# Buck_Boost_Converter_B.net
KiCad netlist of a schematic drawn in Altium Designer
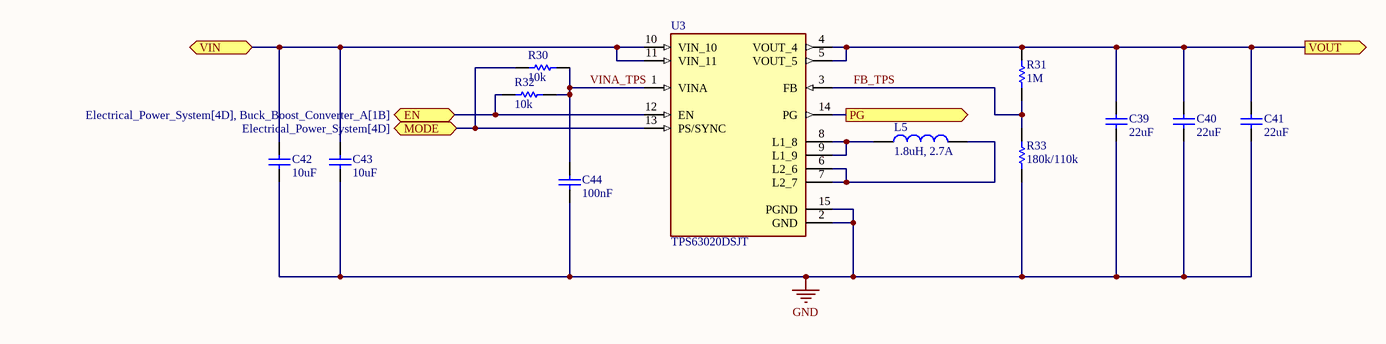
[diagram p0: Buck_Boost_Converter_B.SchDoc]

(export (version "E")
  (design (tool "Eeschema 10.0.6"))
  (components
    (comp (ref "C39")
      (value "22uF")
      (footprint "CAP-SM-0603")
      (description "Capacitor")
      (fields (field (name "Comment") "Cap Non-Pol SMD"))
      (libsource (lib "PIF_Library") (part "Cap Non-Pol SMD"))
    )
    (comp (ref "C40")
      (value "22uF")
      (footprint "CAP-SM-0603")
      (description "Capacitor")
      (fields (field (name "Comment") "Cap Non-Pol SMD"))
      (libsource (lib "PIF_Library") (part "Cap Non-Pol SMD"))
    )
    (comp (ref "C41")
      (value "22uF")
      (footprint "CAP-SM-0603")
      (description "Capacitor")
      (fields (field (name "Comment") "Cap Non-Pol SMD"))
      (libsource (lib "PIF_Library") (part "Cap Non-Pol SMD"))
    )
    (comp (ref "C42")
      (value "10uF")
      (footprint "CAP-SM-0603")
      (description "Capacitor")
      (fields (field (name "Comment") "Cap Non-Pol SMD"))
      (libsource (lib "PIF_Library") (part "Cap Non-Pol SMD"))
    )
    (comp (ref "C43")
      (value "10uF")
      (footprint "CAP-SM-0603")
      (description "Capacitor")
      (fields (field (name "Comment") "Cap Non-Pol SMD"))
      (libsource (lib "PIF_Library") (part "Cap Non-Pol SMD"))
    )
    (comp (ref "C44")
      (value "100nF")
      (footprint "CAP-SM-0603")
      (description "Capacitor")
      (fields (field (name "Comment") "Cap Non-Pol SMD"))
      (libsource (lib "PIF_Library") (part "Cap Non-Pol SMD"))
    )
    (comp (ref "L5")
      (value "1.8uH, 2.7A")
      (footprint "WE-PD2A_4532")
      (description "WE-PD2A SMT Power Inductor, size 4532, 1.8uH, 2.7A")
      (fields
        (field (name "MANUFACTURER PART NUMBER") "784773018")
        (field (name "MANUFACTURER") "Wurth Elektronik")
      )
      (libsource (lib "Altium_Coil_Inductor") (part "784773018"))
    )
    (comp (ref "R30")
      (value "10k")
      (footprint "RES-SM-0603")
      (description "Resistor")
      (fields (field (name "Comment") "RESISTOR SMD"))
      (libsource (lib "PIF_Library") (part "RESISTOR SMD"))
    )
    (comp (ref "R31")
      (value "1M")
      (footprint "RES-SM-0603")
      (description "Resistor")
      (fields (field (name "Comment") "RESISTOR SMD"))
      (libsource (lib "PIF_Library") (part "RESISTOR SMD"))
    )
    (comp (ref "R32")
      (value "10k")
      (footprint "RES-SM-0603")
      (description "Resistor")
      (fields (field (name "Comment") "RESISTOR SMD"))
      (libsource (lib "PIF_Library") (part "RESISTOR SMD"))
    )
    (comp (ref "R33")
      (value "180k/110k")
      (footprint "RES-SM-0603")
      (description "Resistor")
      (fields (field (name "Comment") "RESISTOR SMD"))
      (libsource (lib "PIF_Library") (part "RESISTOR SMD"))
    )
    (comp (ref "U3")
      (value "TPS63020DSJT")
      (footprint "IC_TPS63020DSJT")
      (description "High Efficiency Single Inductor Buck-Boost Converter with 4A Switch 14-VSON -40 to 85")
      (fields (field (name "MF") "Texas Instruments"))
      (libsource (lib "EPS_Board_Lib") (part "TPS63020DSJT"))
    )
  )
  (nets
    (net (code "1") (name "/EN") (class "Default")
      (node (ref "R32") (pin "2") (pinfunction "2_2") (pintype "passive"))
      (node (ref "U3") (pin "12") (pinfunction "EN_12") (pintype "input"))
    )
    (net (code "2") (name "/FB_TPS") (class "Default")
      (node (ref "R31") (pin "1") (pinfunction "1_1") (pintype "passive"))
      (node (ref "R33") (pin "2") (pinfunction "2_2") (pintype "passive"))
      (node (ref "U3") (pin "3") (pinfunction "FB_3") (pintype "input"))
    )
    (net (code "3") (name "/MODE") (class "Default")
      (node (ref "R30") (pin "2") (pinfunction "2_2") (pintype "passive"))
      (node (ref "U3") (pin "13") (pinfunction "PS/SYNC_13") (pintype "input"))
    )
    (net (code "4") (name "/PG") (class "Default")
      (node (ref "U3") (pin "14") (pinfunction "PG_14") (pintype "output"))
    )
    (net (code "5") (name "/VIN") (class "Default")
      (node (ref "C42") (pin "2") (pinfunction "2_2") (pintype "passive"))
      (node (ref "C43") (pin "2") (pinfunction "2_2") (pintype "passive"))
      (node (ref "U3") (pin "10") (pinfunction "VIN_10_10") (pintype "input"))
      (node (ref "U3") (pin "11") (pinfunction "VIN_11_11") (pintype "input"))
    )
    (net (code "6") (name "/VINA_TPS") (class "Default")
      (node (ref "C44") (pin "2") (pinfunction "2_2") (pintype "passive"))
      (node (ref "R30") (pin "1") (pinfunction "1_1") (pintype "passive"))
      (node (ref "R32") (pin "1") (pinfunction "1_1") (pintype "passive"))
      (node (ref "U3") (pin "1") (pinfunction "VINA_1") (pintype "input"))
    )
    (net (code "7") (name "/VOUT") (class "Default")
      (node (ref "C39") (pin "2") (pinfunction "2_2") (pintype "passive"))
      (node (ref "C40") (pin "2") (pinfunction "2_2") (pintype "passive"))
      (node (ref "C41") (pin "2") (pinfunction "2_2") (pintype "passive"))
      (node (ref "R31") (pin "2") (pinfunction "2_2") (pintype "passive"))
      (node (ref "U3") (pin "4") (pinfunction "VOUT_4_4") (pintype "output"))
      (node (ref "U3") (pin "5") (pinfunction "VOUT_5_5") (pintype "output"))
    )
    (net (code "8") (name "GND") (class "Default")
      (node (ref "C39") (pin "1") (pinfunction "1_1") (pintype "passive"))
      (node (ref "C40") (pin "1") (pinfunction "1_1") (pintype "passive"))
      (node (ref "C41") (pin "1") (pinfunction "1_1") (pintype "passive"))
      (node (ref "C42") (pin "1") (pinfunction "1_1") (pintype "passive"))
      (node (ref "C43") (pin "1") (pinfunction "1_1") (pintype "passive"))
      (node (ref "C44") (pin "1") (pinfunction "1_1") (pintype "passive"))
      (node (ref "R33") (pin "1") (pinfunction "1_1") (pintype "passive"))
      (node (ref "U3") (pin "15") (pinfunction "PGND_15") (pintype "power_in"))
      (node (ref "U3") (pin "2") (pinfunction "GND_2") (pintype "power_in"))
    )
    (net (code "9") (name "Net-(U3-L1_8)") (class "Default")
      (node (ref "L5") (pin "1") (pinfunction "1_1") (pintype "passive"))
      (node (ref "U3") (pin "8") (pinfunction "L1_8_8") (pintype "passive"))
      (node (ref "U3") (pin "9") (pinfunction "L1_9_9") (pintype "passive"))
    )
    (net (code "10") (name "Net-(U3-L2_6)") (class "Default")
      (node (ref "L5") (pin "2") (pinfunction "2_2") (pintype "passive"))
      (node (ref "U3") (pin "6") (pinfunction "L2_6_6") (pintype "passive"))
      (node (ref "U3") (pin "7") (pinfunction "L2_7_7") (pintype "passive"))
    )
  )
)
